# SCH_BSPD_Sensorboard.net
KiCad netlist of a schematic drawn in Altium Designer
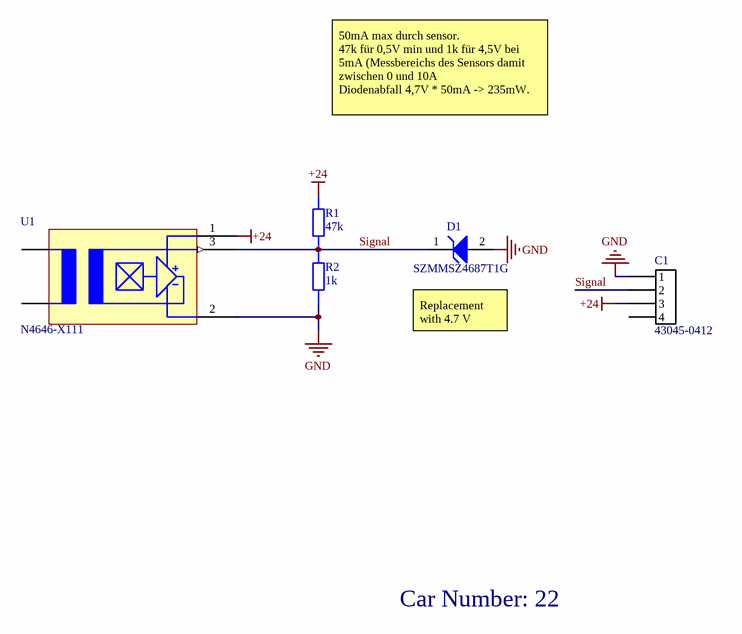
[diagram p0: SCH_BSPD_Sensorboard.SchDoc]

(export (version "E")
  (design (tool "Eeschema 10.0.6"))
  (components
    (comp (ref "C1")
      (value "43045-0412")
      (footprint "43045-0412")
      (description "Molex Micro-Fit 3.0 4-Pin\r\n600V\r\n8.5A")
      (libsource (lib "Standardbauteile") (part "MicroFit3.0 4-Pin"))
    )
    (comp (ref "D1")
      (value "SZMMSZ4687T1G")
      (footprint "ONSC-SOD-123-2-425-04_V")
      (description "Zener Voltage Regulator, 500 mW, 2-Pin SOD-123, Pb-Free, Tape and Reel")
      (fields (field (name "MANUFACTURER") "On Semiconductor"))
      (libsource (lib "Altium Content Vault") (part "ONSC-K1A2-2"))
    )
    (comp (ref "R1")
      (value "47k")
      (footprint "STACKPOLE CSR0603")
      (description "Resistor with multiple footprints")
      (fields (field (name "POWER") "0.1W") (field (name "Comment") "SMD Resistor"))
      (libsource (lib "Standardbauteile") (part "SMD Resistor"))
    )
    (comp (ref "R2")
      (value "1k")
      (footprint "STACKPOLE CSR0603")
      (description "Resistor with multiple footprints")
      (fields (field (name "POWER") "0.1W") (field (name "Comment") "SMD Resistor"))
      (libsource (lib "Standardbauteile") (part "SMD Resistor"))
    )
    (comp (ref "U1")
      (value "N4646-X111")
      (footprint "N4646-X100")
      (libsource (lib "Integrated_LibraryLukas_New") (part "N4646-X100"))
    )
  )
  (nets
    (net (code "1") (name "+24") (class "Default")
      (node (ref "C1") (pin "3") (pinfunction "3_3") (pintype "passive"))
      (node (ref "R1") (pin "2") (pinfunction "2_2") (pintype "passive"))
      (node (ref "U1") (pin "1") (pinfunction "V_cc_1") (pintype "power_in"))
    )
    (net (code "2") (name "/Signal") (class "Default")
      (node (ref "C1") (pin "2") (pinfunction "2_2") (pintype "passive"))
      (node (ref "D1") (pin "1") (pinfunction "K_1") (pintype "passive"))
      (node (ref "R1") (pin "1") (pinfunction "1_1") (pintype "passive"))
      (node (ref "R2") (pin "2") (pinfunction "2_2") (pintype "passive"))
      (node (ref "U1") (pin "3") (pinfunction "I_s_3") (pintype "output"))
    )
    (net (code "3") (name "GND") (class "Default")
      (node (ref "C1") (pin "1") (pinfunction "1_1") (pintype "passive"))
      (node (ref "D1") (pin "2") (pinfunction "A_2") (pintype "passive"))
      (node (ref "R2") (pin "1") (pinfunction "1_1") (pintype "passive"))
      (node (ref "U1") (pin "2") (pinfunction "-V_cc_2") (pintype "power_in"))
    )
    (net (code "4") (name "unconnected-(C1-Pad4)") (class "Default")
      (node (ref "C1") (pin "4") (pinfunction "4_4") (pintype "passive"))
    )
  )
)
